# apresenta_o1.net
KiCad netlist of a schematic drawn in EAGLE
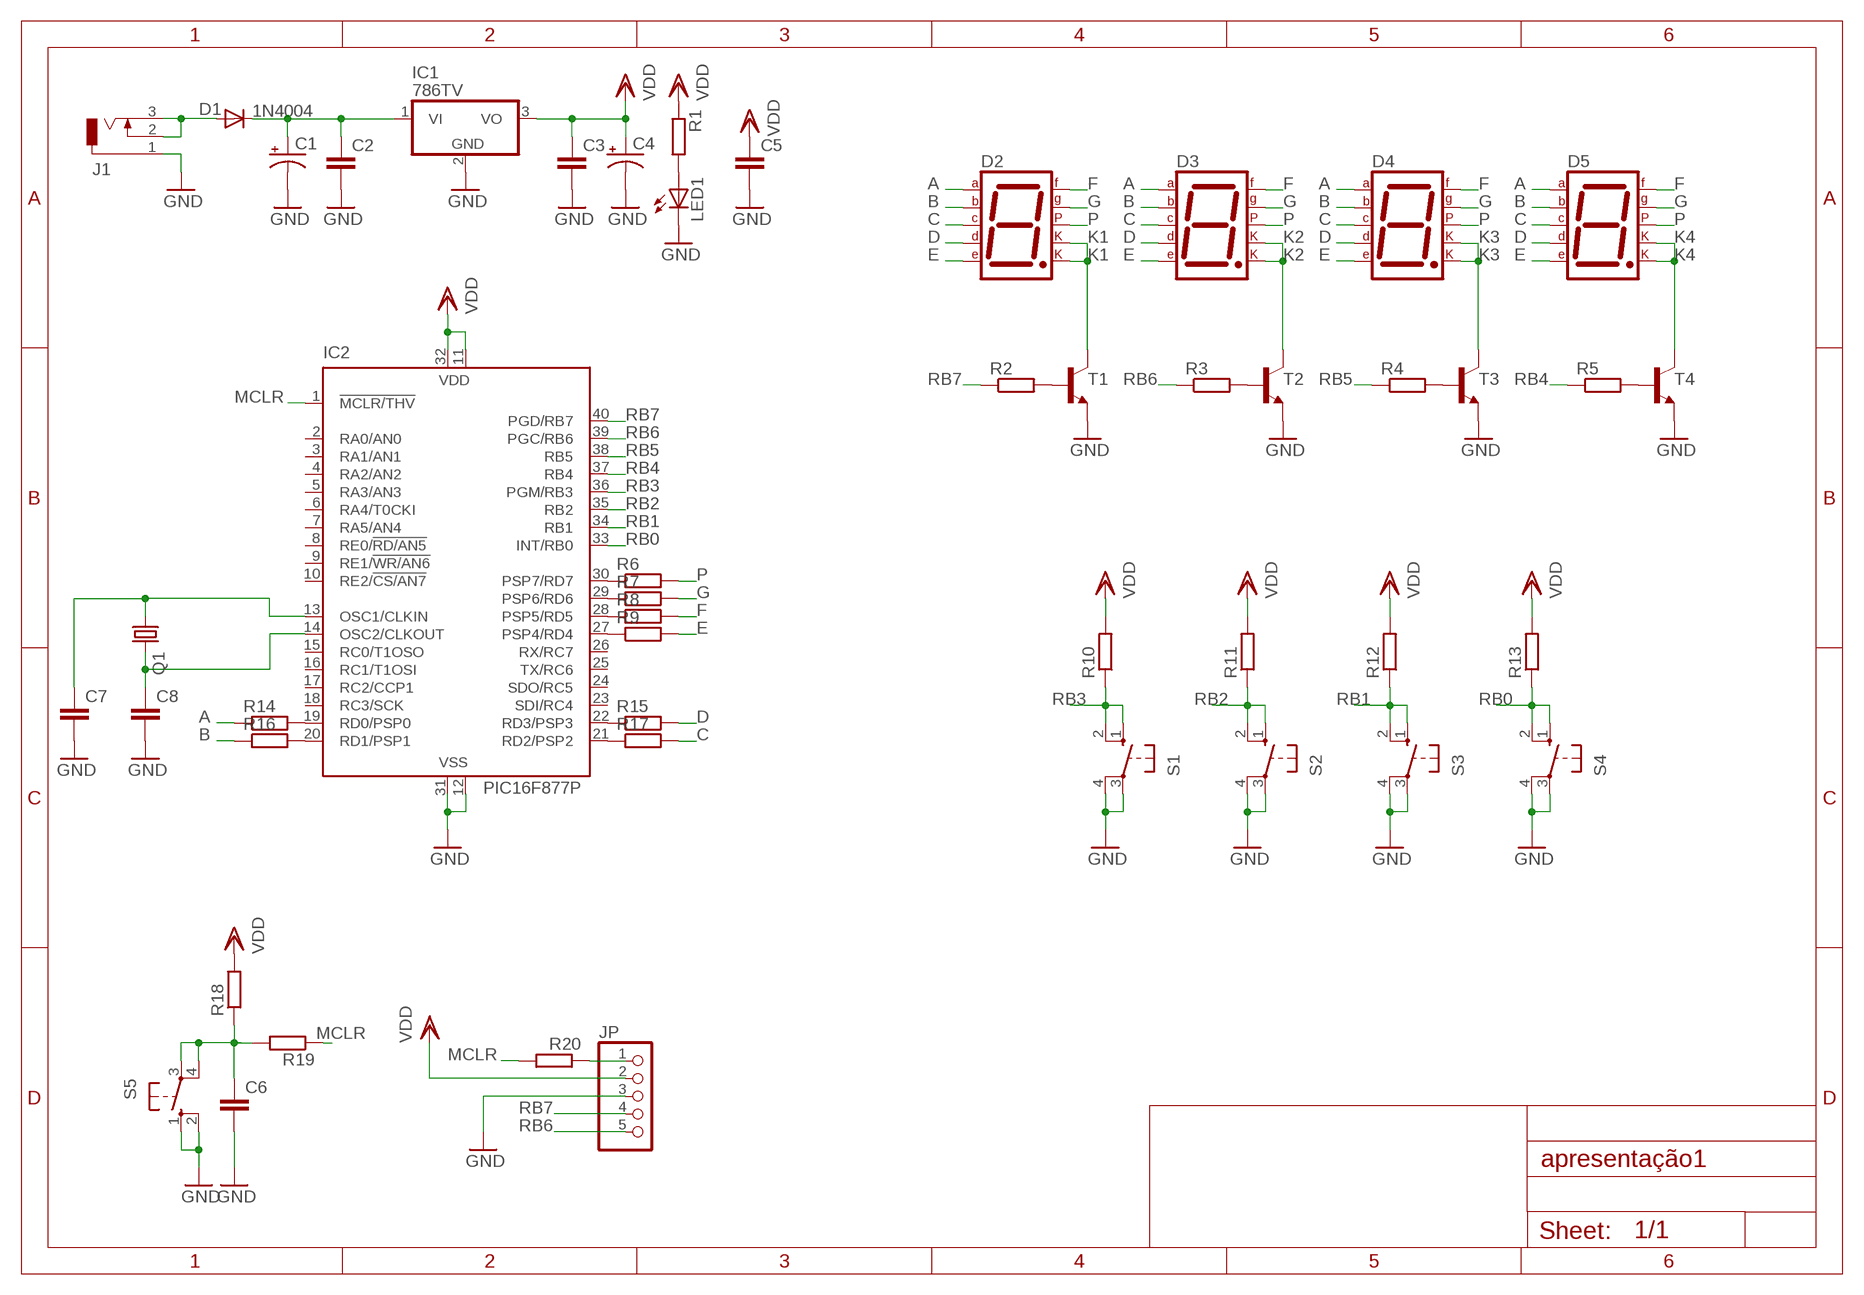
[diagram p0: schematic, sheet 1]

(export (version "E")
  (design (tool "Eeschema 10.0.6"))
  (components
    (comp (ref "C1")
      (value "CPOL-USE2.5-5")
      (footprint "eagle-import:E2,5-5")
      (libsource (lib "eagle-import") (part "CPOL-USE2.5-5"))
    )
    (comp (ref "C2")
      (value "C-EU025-025X050")
      (footprint "eagle-import:C025-025X050")
      (libsource (lib "eagle-import") (part "C-EU025-025X050"))
    )
    (comp (ref "C3")
      (value "C-EU025-025X050")
      (footprint "eagle-import:C025-025X050")
      (libsource (lib "eagle-import") (part "C-EU025-025X050"))
    )
    (comp (ref "C4")
      (value "CPOL-USE2.5-5")
      (footprint "eagle-import:E2,5-5")
      (libsource (lib "eagle-import") (part "CPOL-USE2.5-5"))
    )
    (comp (ref "C5")
      (value "C-EU025-025X050")
      (footprint "eagle-import:C025-025X050")
      (libsource (lib "eagle-import") (part "C-EU025-025X050"))
    )
    (comp (ref "C6")
      (value "C-EU025-025X050")
      (footprint "eagle-import:C025-025X050")
      (libsource (lib "eagle-import") (part "C-EU025-025X050"))
    )
    (comp (ref "C7")
      (value "C-EU025-025X050")
      (footprint "eagle-import:C025-025X050")
      (libsource (lib "eagle-import") (part "C-EU025-025X050"))
    )
    (comp (ref "C8")
      (value "C-EU025-025X050")
      (footprint "eagle-import:C025-025X050")
      (libsource (lib "eagle-import") (part "C-EU025-025X050"))
    )
    (comp (ref "D1")
      (value "1N4004")
      (footprint "eagle-import:DO41-10")
      (libsource (lib "eagle-import") (part "1N4004"))
    )
    (comp (ref "D2")
      (value "7SEG-CK")
      (footprint "eagle-import:7SEG-13")
      (libsource (lib "eagle-import") (part "7SEG-CK"))
    )
    (comp (ref "D3")
      (value "7SEG-CK")
      (footprint "eagle-import:7SEG-13")
      (libsource (lib "eagle-import") (part "7SEG-CK"))
    )
    (comp (ref "D4")
      (value "7SEG-CK")
      (footprint "eagle-import:7SEG-13")
      (libsource (lib "eagle-import") (part "7SEG-CK"))
    )
    (comp (ref "D5")
      (value "7SEG-CK")
      (footprint "eagle-import:7SEG-13")
      (libsource (lib "eagle-import") (part "7SEG-CK"))
    )
    (comp (ref "IC1")
      (value "786TV")
      (footprint "eagle-import:TO220V")
      (libsource (lib "eagle-import") (part "78TV6"))
    )
    (comp (ref "IC2")
      (value "PIC16F877P")
      (footprint "eagle-import:DIL40")
      (fields (field (name "MF") "MICROCHIP") (field (name "MPN") "PIC16F877-04/P"))
      (libsource (lib "eagle-import") (part "PIC16F87P7"))
    )
    (comp (ref "J1")
      (value "DCJ0303")
      (footprint "eagle-import:DCJ0303")
      (libsource (lib "eagle-import") (part "DCJ0303"))
    )
    (comp (ref "JP")
      (value "PINHD-1X5")
      (footprint "eagle-import:1X05")
      (libsource (lib "eagle-import") (part "PINHD-1X5"))
    )
    (comp (ref "LED1")
      (value "LED5MM")
      (footprint "eagle-import:LED5MM")
      (libsource (lib "eagle-import") (part "LED5MM"))
    )
    (comp (ref "Q1")
      (value "CRYSTALHC49S")
      (footprint "eagle-import:HC49_S")
      (libsource (lib "eagle-import") (part "CRYSTALHC49S"))
    )
    (comp (ref "R1")
      (value "R-EU_0204/7")
      (footprint "eagle-import:0204_7")
      (libsource (lib "eagle-import") (part "R-EU_0204/7"))
    )
    (comp (ref "R2")
      (value "R-EU_0204/7")
      (footprint "eagle-import:0204_7")
      (libsource (lib "eagle-import") (part "R-EU_0204/7"))
    )
    (comp (ref "R3")
      (value "R-EU_0204/7")
      (footprint "eagle-import:0204_7")
      (libsource (lib "eagle-import") (part "R-EU_0204/7"))
    )
    (comp (ref "R4")
      (value "R-EU_0204/7")
      (footprint "eagle-import:0204_7")
      (libsource (lib "eagle-import") (part "R-EU_0204/7"))
    )
    (comp (ref "R5")
      (value "R-EU_0204/7")
      (footprint "eagle-import:0204_7")
      (libsource (lib "eagle-import") (part "R-EU_0204/7"))
    )
    (comp (ref "R6")
      (value "R-EU_0204/7")
      (footprint "eagle-import:0204_7")
      (libsource (lib "eagle-import") (part "R-EU_0204/7"))
    )
    (comp (ref "R7")
      (value "R-EU_0204/7")
      (footprint "eagle-import:0204_7")
      (libsource (lib "eagle-import") (part "R-EU_0204/7"))
    )
    (comp (ref "R8")
      (value "R-EU_0204/7")
      (footprint "eagle-import:0204_7")
      (libsource (lib "eagle-import") (part "R-EU_0204/7"))
    )
    (comp (ref "R9")
      (value "R-EU_0204/7")
      (footprint "eagle-import:0204_7")
      (libsource (lib "eagle-import") (part "R-EU_0204/7"))
    )
    (comp (ref "R10")
      (value "R-EU_0204/7")
      (footprint "eagle-import:0204_7")
      (libsource (lib "eagle-import") (part "R-EU_0204/7"))
    )
    (comp (ref "R11")
      (value "R-EU_0204/7")
      (footprint "eagle-import:0204_7")
      (libsource (lib "eagle-import") (part "R-EU_0204/7"))
    )
    (comp (ref "R12")
      (value "R-EU_0204/7")
      (footprint "eagle-import:0204_7")
      (libsource (lib "eagle-import") (part "R-EU_0204/7"))
    )
    (comp (ref "R13")
      (value "R-EU_0204/7")
      (footprint "eagle-import:0204_7")
      (libsource (lib "eagle-import") (part "R-EU_0204/7"))
    )
    (comp (ref "R14")
      (value "R-EU_0204/7")
      (footprint "eagle-import:0204_7")
      (libsource (lib "eagle-import") (part "R-EU_0204/7"))
    )
    (comp (ref "R15")
      (value "R-EU_0204/7")
      (footprint "eagle-import:0204_7")
      (libsource (lib "eagle-import") (part "R-EU_0204/7"))
    )
    (comp (ref "R16")
      (value "R-EU_0204/7")
      (footprint "eagle-import:0204_7")
      (libsource (lib "eagle-import") (part "R-EU_0204/7"))
    )
    (comp (ref "R17")
      (value "R-EU_0204/7")
      (footprint "eagle-import:0204_7")
      (libsource (lib "eagle-import") (part "R-EU_0204/7"))
    )
    (comp (ref "R18")
      (value "R-EU_0204/7")
      (footprint "eagle-import:0204_7")
      (libsource (lib "eagle-import") (part "R-EU_0204/7"))
    )
    (comp (ref "R19")
      (value "R-EU_0204/7")
      (footprint "eagle-import:0204_7")
      (libsource (lib "eagle-import") (part "R-EU_0204/7"))
    )
    (comp (ref "R20")
      (value "R-EU_0204/7")
      (footprint "eagle-import:0204_7")
      (libsource (lib "eagle-import") (part "R-EU_0204/7"))
    )
    (comp (ref "S1")
      (value "10-XX")
      (footprint "eagle-import:B3F-10XX")
      (fields (field (name "MPN") "B3F-1000"))
      (libsource (lib "eagle-import") (part "10-XX"))
    )
    (comp (ref "S2")
      (value "10-XX")
      (footprint "eagle-import:B3F-10XX")
      (fields (field (name "MPN") "B3F-1000"))
      (libsource (lib "eagle-import") (part "10-XX"))
    )
    (comp (ref "S3")
      (value "10-XX")
      (footprint "eagle-import:B3F-10XX")
      (fields (field (name "MPN") "B3F-1000"))
      (libsource (lib "eagle-import") (part "10-XX"))
    )
    (comp (ref "S4")
      (value "10-XX")
      (footprint "eagle-import:B3F-10XX")
      (fields (field (name "MPN") "B3F-1000"))
      (libsource (lib "eagle-import") (part "10-XX"))
    )
    (comp (ref "S5")
      (value "10-XX")
      (footprint "eagle-import:B3F-10XX")
      (fields
        (field (name "MPN") "B3F-1000")
        (field (name "MPN_1") "B3F-1000")
        (field (name "OC_FARNELL") "176432")
        (field (name "OC_NEWARK") "36M3542")
      )
      (libsource (lib "eagle-import") (part "10-XX"))
    )
    (comp (ref "T1")
      (value "BC337-16-NPN-TO92-CBE")
      (footprint "eagle-import:TO92-CBE")
      (libsource (lib "eagle-import") (part "-NPN-TO92-CBEBC337-16"))
    )
    (comp (ref "T2")
      (value "BC337-16-NPN-TO92-CBE")
      (footprint "eagle-import:TO92-CBE")
      (libsource (lib "eagle-import") (part "-NPN-TO92-CBEBC337-16"))
    )
    (comp (ref "T3")
      (value "BC337-16-NPN-TO92-CBE")
      (footprint "eagle-import:TO92-CBE")
      (libsource (lib "eagle-import") (part "-NPN-TO92-CBEBC337-16"))
    )
    (comp (ref "T4")
      (value "BC337-16-NPN-TO92-CBE")
      (footprint "eagle-import:TO92-CBE")
      (libsource (lib "eagle-import") (part "-NPN-TO92-CBEBC337-16"))
    )
  )
  (nets
    (net (code "1") (name "/A") (class "Default")
      (node (ref "D2") (pin "7") (pinfunction "A_7") (pintype "passive"))
      (node (ref "D3") (pin "7") (pinfunction "A_7") (pintype "passive"))
      (node (ref "D4") (pin "7") (pinfunction "A_7") (pintype "passive"))
      (node (ref "D5") (pin "7") (pinfunction "A_7") (pintype "passive"))
      (node (ref "R14") (pin "1") (pinfunction "1_1") (pintype "passive"))
    )
    (net (code "2") (name "/B") (class "Default")
      (node (ref "D2") (pin "6") (pinfunction "B_6") (pintype "passive"))
      (node (ref "D3") (pin "6") (pinfunction "B_6") (pintype "passive"))
      (node (ref "D4") (pin "6") (pinfunction "B_6") (pintype "passive"))
      (node (ref "D5") (pin "6") (pinfunction "B_6") (pintype "passive"))
      (node (ref "R16") (pin "1") (pinfunction "1_1") (pintype "passive"))
    )
    (net (code "3") (name "/C") (class "Default")
      (node (ref "D2") (pin "4") (pinfunction "C_4") (pintype "passive"))
      (node (ref "D3") (pin "4") (pinfunction "C_4") (pintype "passive"))
      (node (ref "D4") (pin "4") (pinfunction "C_4") (pintype "passive"))
      (node (ref "D5") (pin "4") (pinfunction "C_4") (pintype "passive"))
      (node (ref "R17") (pin "2") (pinfunction "2_2") (pintype "passive"))
    )
    (net (code "4") (name "/D") (class "Default")
      (node (ref "D2") (pin "2") (pinfunction "D_2") (pintype "passive"))
      (node (ref "D3") (pin "2") (pinfunction "D_2") (pintype "passive"))
      (node (ref "D4") (pin "2") (pinfunction "D_2") (pintype "passive"))
      (node (ref "D5") (pin "2") (pinfunction "D_2") (pintype "passive"))
      (node (ref "R15") (pin "2") (pinfunction "2_2") (pintype "passive"))
    )
    (net (code "5") (name "/E") (class "Default")
      (node (ref "D2") (pin "1") (pinfunction "E_1") (pintype "passive"))
      (node (ref "D3") (pin "1") (pinfunction "E_1") (pintype "passive"))
      (node (ref "D4") (pin "1") (pinfunction "E_1") (pintype "passive"))
      (node (ref "D5") (pin "1") (pinfunction "E_1") (pintype "passive"))
      (node (ref "R9") (pin "2") (pinfunction "2_2") (pintype "passive"))
    )
    (net (code "6") (name "/F") (class "Default")
      (node (ref "D2") (pin "9") (pinfunction "F_9") (pintype "passive"))
      (node (ref "D3") (pin "9") (pinfunction "F_9") (pintype "passive"))
      (node (ref "D4") (pin "9") (pinfunction "F_9") (pintype "passive"))
      (node (ref "D5") (pin "9") (pinfunction "F_9") (pintype "passive"))
      (node (ref "R8") (pin "2") (pinfunction "2_2") (pintype "passive"))
    )
    (net (code "7") (name "/G") (class "Default")
      (node (ref "D2") (pin "10") (pinfunction "G_10") (pintype "passive"))
      (node (ref "D3") (pin "10") (pinfunction "G_10") (pintype "passive"))
      (node (ref "D4") (pin "10") (pinfunction "G_10") (pintype "passive"))
      (node (ref "D5") (pin "10") (pinfunction "G_10") (pintype "passive"))
      (node (ref "R7") (pin "2") (pinfunction "2_2") (pintype "passive"))
    )
    (net (code "8") (name "/K1") (class "Default")
      (node (ref "D2") (pin "3") (pinfunction "CK1_3") (pintype "passive"))
      (node (ref "D2") (pin "8") (pinfunction "CK2_8") (pintype "passive"))
      (node (ref "T1") (pin "C") (pinfunction "C_C") (pintype "passive"))
    )
    (net (code "9") (name "/K2") (class "Default")
      (node (ref "D3") (pin "3") (pinfunction "CK1_3") (pintype "passive"))
      (node (ref "D3") (pin "8") (pinfunction "CK2_8") (pintype "passive"))
      (node (ref "T2") (pin "C") (pinfunction "C_C") (pintype "passive"))
    )
    (net (code "10") (name "/K3") (class "Default")
      (node (ref "D4") (pin "3") (pinfunction "CK1_3") (pintype "passive"))
      (node (ref "D4") (pin "8") (pinfunction "CK2_8") (pintype "passive"))
      (node (ref "T3") (pin "C") (pinfunction "C_C") (pintype "passive"))
    )
    (net (code "11") (name "/K4") (class "Default")
      (node (ref "D5") (pin "3") (pinfunction "CK1_3") (pintype "passive"))
      (node (ref "D5") (pin "8") (pinfunction "CK2_8") (pintype "passive"))
      (node (ref "T4") (pin "C") (pinfunction "C_C") (pintype "passive"))
    )
    (net (code "12") (name "/MCLR") (class "Default")
      (node (ref "IC2") (pin "1") (pinfunction "~{MCLR/THV}_1") (pintype "input"))
      (node (ref "R19") (pin "1") (pinfunction "1_1") (pintype "passive"))
      (node (ref "R20") (pin "2") (pinfunction "2_2") (pintype "passive"))
    )
    (net (code "13") (name "/P") (class "Default")
      (node (ref "D2") (pin "5") (pinfunction "DP_5") (pintype "passive"))
      (node (ref "D3") (pin "5") (pinfunction "DP_5") (pintype "passive"))
      (node (ref "D4") (pin "5") (pinfunction "DP_5") (pintype "passive"))
      (node (ref "D5") (pin "5") (pinfunction "DP_5") (pintype "passive"))
      (node (ref "R6") (pin "2") (pinfunction "2_2") (pintype "passive"))
    )
    (net (code "14") (name "/RB0") (class "Default")
      (node (ref "IC2") (pin "33") (pinfunction "INT/RB0_33") (pintype "bidirectional"))
      (node (ref "R13") (pin "1") (pinfunction "1_1") (pintype "passive"))
      (node (ref "S4") (pin "1") (pinfunction "S_1") (pintype "passive"))
      (node (ref "S4") (pin "2") (pinfunction "S1_2") (pintype "passive"))
    )
    (net (code "15") (name "/RB1") (class "Default")
      (node (ref "IC2") (pin "34") (pinfunction "RB1_34") (pintype "bidirectional"))
      (node (ref "R12") (pin "1") (pinfunction "1_1") (pintype "passive"))
      (node (ref "S3") (pin "1") (pinfunction "S_1") (pintype "passive"))
      (node (ref "S3") (pin "2") (pinfunction "S1_2") (pintype "passive"))
    )
    (net (code "16") (name "/RB2") (class "Default")
      (node (ref "IC2") (pin "35") (pinfunction "RB2_35") (pintype "bidirectional"))
      (node (ref "R11") (pin "1") (pinfunction "1_1") (pintype "passive"))
      (node (ref "S2") (pin "1") (pinfunction "S_1") (pintype "passive"))
      (node (ref "S2") (pin "2") (pinfunction "S1_2") (pintype "passive"))
    )
    (net (code "17") (name "/RB3") (class "Default")
      (node (ref "IC2") (pin "36") (pinfunction "PGM/RB3_36") (pintype "bidirectional"))
      (node (ref "R10") (pin "1") (pinfunction "1_1") (pintype "passive"))
      (node (ref "S1") (pin "1") (pinfunction "S_1") (pintype "passive"))
      (node (ref "S1") (pin "2") (pinfunction "S1_2") (pintype "passive"))
    )
    (net (code "18") (name "/RB4") (class "Default")
      (node (ref "IC2") (pin "37") (pinfunction "RB4_37") (pintype "bidirectional"))
      (node (ref "R5") (pin "1") (pinfunction "1_1") (pintype "passive"))
    )
    (net (code "19") (name "/RB5") (class "Default")
      (node (ref "IC2") (pin "38") (pinfunction "RB5_38") (pintype "bidirectional"))
      (node (ref "R4") (pin "1") (pinfunction "1_1") (pintype "passive"))
    )
    (net (code "20") (name "/RB6") (class "Default")
      (node (ref "IC2") (pin "39") (pinfunction "PGC/RB6_39") (pintype "bidirectional"))
      (node (ref "JP") (pin "5") (pinfunction "5_5") (pintype "passive"))
      (node (ref "R3") (pin "1") (pinfunction "1_1") (pintype "passive"))
    )
    (net (code "21") (name "/RB7") (class "Default")
      (node (ref "IC2") (pin "40") (pinfunction "PGD/RB7_40") (pintype "bidirectional"))
      (node (ref "JP") (pin "4") (pinfunction "4_4") (pintype "passive"))
      (node (ref "R2") (pin "1") (pinfunction "1_1") (pintype "passive"))
    )
    (net (code "22") (name "GND") (class "Default")
      (node (ref "C1") (pin "-") (pinfunction "-_-") (pintype "passive"))
      (node (ref "C2") (pin "2") (pinfunction "2_2") (pintype "passive"))
      (node (ref "C3") (pin "2") (pinfunction "2_2") (pintype "passive"))
      (node (ref "C4") (pin "-") (pinfunction "-_-") (pintype "passive"))
      (node (ref "C5") (pin "2") (pinfunction "2_2") (pintype "passive"))
      (node (ref "C6") (pin "2") (pinfunction "2_2") (pintype "passive"))
      (node (ref "C7") (pin "2") (pinfunction "2_2") (pintype "passive"))
      (node (ref "C8") (pin "2") (pinfunction "2_2") (pintype "passive"))
      (node (ref "IC1") (pin "2") (pinfunction "GND_2") (pintype "passive"))
      (node (ref "IC2") (pin "12") (pinfunction "VSS_12") (pintype "power_in"))
      (node (ref "IC2") (pin "31") (pinfunction "VSS_31") (pintype "power_in"))
      (node (ref "J1") (pin "1") (pinfunction "1_1") (pintype "passive"))
      (node (ref "JP") (pin "3") (pinfunction "3_3") (pintype "passive"))
      (node (ref "LED1") (pin "K") (pinfunction "C_K") (pintype "passive"))
      (node (ref "S1") (pin "3") (pinfunction "P_3") (pintype "passive"))
      (node (ref "S1") (pin "4") (pinfunction "P1_4") (pintype "passive"))
      (node (ref "S2") (pin "3") (pinfunction "P_3") (pintype "passive"))
      (node (ref "S2") (pin "4") (pinfunction "P1_4") (pintype "passive"))
      (node (ref "S3") (pin "3") (pinfunction "P_3") (pintype "passive"))
      (node (ref "S3") (pin "4") (pinfunction "P1_4") (pintype "passive"))
      (node (ref "S4") (pin "3") (pinfunction "P_3") (pintype "passive"))
      (node (ref "S4") (pin "4") (pinfunction "P1_4") (pintype "passive"))
      (node (ref "S5") (pin "1") (pinfunction "S_1") (pintype "passive"))
      (node (ref "S5") (pin "2") (pinfunction "S1_2") (pintype "passive"))
      (node (ref "T1") (pin "E") (pinfunction "E_E") (pintype "passive"))
      (node (ref "T2") (pin "E") (pinfunction "E_E") (pintype "passive"))
      (node (ref "T3") (pin "E") (pinfunction "E_E") (pintype "passive"))
      (node (ref "T4") (pin "E") (pinfunction "E_E") (pintype "passive"))
    )
    (net (code "23") (name "Net-(D1-PadA)") (class "Default")
      (node (ref "D1") (pin "A") (pinfunction "A_A") (pintype "passive"))
      (node (ref "J1") (pin "2") (pinfunction "2_2") (pintype "passive"))
      (node (ref "J1") (pin "3") (pinfunction "3_3") (pintype "passive"))
    )
    (net (code "24") (name "Net-(IC1-VI)") (class "Default")
      (node (ref "C1") (pin "+") (pinfunction "+_+") (pintype "passive"))
      (node (ref "C2") (pin "1") (pinfunction "1_1") (pintype "passive"))
      (node (ref "D1") (pin "C") (pinfunction "C_C") (pintype "passive"))
      (node (ref "IC1") (pin "1") (pinfunction "VI_1") (pintype "input"))
    )
    (net (code "25") (name "Net-(IC2-OSC1{slash}CLKIN)") (class "Default")
      (node (ref "C7") (pin "1") (pinfunction "1_1") (pintype "passive"))
      (node (ref "IC2") (pin "13") (pinfunction "OSC1/CLKIN_13") (pintype "input"))
      (node (ref "Q1") (pin "1") (pinfunction "1_1") (pintype "passive"))
    )
    (net (code "26") (name "Net-(IC2-OSC2{slash}CLKOUT)") (class "Default")
      (node (ref "C8") (pin "1") (pinfunction "1_1") (pintype "passive"))
      (node (ref "IC2") (pin "14") (pinfunction "OSC2/CLKOUT_14") (pintype "output"))
      (node (ref "Q1") (pin "2") (pinfunction "2_2") (pintype "passive"))
    )
    (net (code "27") (name "Net-(IC2-PSP4{slash}RD4)") (class "Default")
      (node (ref "IC2") (pin "27") (pinfunction "PSP4/RD4_27") (pintype "bidirectional"))
      (node (ref "R9") (pin "1") (pinfunction "1_1") (pintype "passive"))
    )
    (net (code "28") (name "Net-(IC2-PSP5{slash}RD5)") (class "Default")
      (node (ref "IC2") (pin "28") (pinfunction "PSP5/RD5_28") (pintype "bidirectional"))
      (node (ref "R8") (pin "1") (pinfunction "1_1") (pintype "passive"))
    )
    (net (code "29") (name "Net-(IC2-PSP6{slash}RD6)") (class "Default")
      (node (ref "IC2") (pin "29") (pinfunction "PSP6/RD6_29") (pintype "bidirectional"))
      (node (ref "R7") (pin "1") (pinfunction "1_1") (pintype "passive"))
    )
    (net (code "30") (name "Net-(IC2-PSP7{slash}RD7)") (class "Default")
      (node (ref "IC2") (pin "30") (pinfunction "PSP7/RD7_30") (pintype "bidirectional"))
      (node (ref "R6") (pin "1") (pinfunction "1_1") (pintype "passive"))
    )
    (net (code "31") (name "Net-(IC2-RD0{slash}PSP0)") (class "Default")
      (node (ref "IC2") (pin "19") (pinfunction "RD0/PSP0_19") (pintype "bidirectional"))
      (node (ref "R14") (pin "2") (pinfunction "2_2") (pintype "passive"))
    )
    (net (code "32") (name "Net-(IC2-RD1{slash}PSP1)") (class "Default")
      (node (ref "IC2") (pin "20") (pinfunction "RD1/PSP1_20") (pintype "bidirectional"))
      (node (ref "R16") (pin "2") (pinfunction "2_2") (pintype "passive"))
    )
    (net (code "33") (name "Net-(IC2-RD2{slash}PSP2)") (class "Default")
      (node (ref "IC2") (pin "21") (pinfunction "RD2/PSP2_21") (pintype "bidirectional"))
      (node (ref "R17") (pin "1") (pinfunction "1_1") (pintype "passive"))
    )
    (net (code "34") (name "Net-(IC2-RD3{slash}PSP3)") (class "Default")
      (node (ref "IC2") (pin "22") (pinfunction "RD3/PSP3_22") (pintype "bidirectional"))
      (node (ref "R15") (pin "1") (pinfunction "1_1") (pintype "passive"))
    )
    (net (code "35") (name "Net-(JP-Pad1)") (class "Default")
      (node (ref "JP") (pin "1") (pinfunction "1_1") (pintype "passive"))
      (node (ref "R20") (pin "1") (pinfunction "1_1") (pintype "passive"))
    )
    (net (code "36") (name "Net-(LED1-PadA)") (class "Default")
      (node (ref "LED1") (pin "A") (pinfunction "A_A") (pintype "passive"))
      (node (ref "R1") (pin "2") (pinfunction "2_2") (pintype "passive"))
    )
    (net (code "37") (name "Net-(R2-Pad2)") (class "Default")
      (node (ref "R2") (pin "2") (pinfunction "2_2") (pintype "passive"))
      (node (ref "T1") (pin "B") (pinfunction "B_B") (pintype "passive"))
    )
    (net (code "38") (name "Net-(R3-Pad2)") (class "Default")
      (node (ref "R3") (pin "2") (pinfunction "2_2") (pintype "passive"))
      (node (ref "T2") (pin "B") (pinfunction "B_B") (pintype "passive"))
    )
    (net (code "39") (name "Net-(R4-Pad2)") (class "Default")
      (node (ref "R4") (pin "2") (pinfunction "2_2") (pintype "passive"))
      (node (ref "T3") (pin "B") (pinfunction "B_B") (pintype "passive"))
    )
    (net (code "40") (name "Net-(R5-Pad2)") (class "Default")
      (node (ref "R5") (pin "2") (pinfunction "2_2") (pintype "passive"))
      (node (ref "T4") (pin "B") (pinfunction "B_B") (pintype "passive"))
    )
    (net (code "41") (name "Net-(S5-P)") (class "Default")
      (node (ref "C6") (pin "1") (pinfunction "1_1") (pintype "passive"))
      (node (ref "R18") (pin "1") (pinfunction "1_1") (pintype "passive"))
      (node (ref "R19") (pin "2") (pinfunction "2_2") (pintype "passive"))
      (node (ref "S5") (pin "3") (pinfunction "P_3") (pintype "passive"))
      (node (ref "S5") (pin "4") (pinfunction "P1_4") (pintype "passive"))
    )
    (net (code "42") (name "VDD") (class "Default")
      (node (ref "C3") (pin "1") (pinfunction "1_1") (pintype "passive"))
      (node (ref "C4") (pin "+") (pinfunction "+_+") (pintype "passive"))
      (node (ref "C5") (pin "1") (pinfunction "1_1") (pintype "passive"))
      (node (ref "IC1") (pin "3") (pinfunction "VO_3") (pintype "passive"))
      (node (ref "IC2") (pin "11") (pinfunction "VDD_11") (pintype "power_in"))
      (node (ref "IC2") (pin "32") (pinfunction "VDD_32") (pintype "power_in"))
      (node (ref "JP") (pin "2") (pinfunction "2_2") (pintype "passive"))
      (node (ref "R1") (pin "1") (pinfunction "1_1") (pintype "passive"))
      (node (ref "R10") (pin "2") (pinfunction "2_2") (pintype "passive"))
      (node (ref "R11") (pin "2") (pinfunction "2_2") (pintype "passive"))
      (node (ref "R12") (pin "2") (pinfunction "2_2") (pintype "passive"))
      (node (ref "R13") (pin "2") (pinfunction "2_2") (pintype "passive"))
      (node (ref "R18") (pin "2") (pinfunction "2_2") (pintype "passive"))
    )
    (net (code "43") (name "unconnected-(IC2-RA0{slash}AN0-Pad2)") (class "Default")
      (node (ref "IC2") (pin "2") (pinfunction "RA0/AN0_2") (pintype "bidirectional"))
    )
    (net (code "44") (name "unconnected-(IC2-RA1{slash}AN1-Pad3)") (class "Default")
      (node (ref "IC2") (pin "3") (pinfunction "RA1/AN1_3") (pintype "bidirectional"))
    )
    (net (code "45") (name "unconnected-(IC2-RA2{slash}AN2-Pad4)") (class "Default")
      (node (ref "IC2") (pin "4") (pinfunction "RA2/AN2_4") (pintype "bidirectional"))
    )
    (net (code "46") (name "unconnected-(IC2-RA3{slash}AN3-Pad5)") (class "Default")
      (node (ref "IC2") (pin "5") (pinfunction "RA3/AN3_5") (pintype "bidirectional"))
    )
    (net (code "47") (name "unconnected-(IC2-RA4{slash}T0CKI-Pad6)") (class "Default")
      (node (ref "IC2") (pin "6") (pinfunction "RA4/T0CKI_6") (pintype "bidirectional"))
    )
    (net (code "48") (name "unconnected-(IC2-RA5{slash}AN4-Pad7)") (class "Default")
      (node (ref "IC2") (pin "7") (pinfunction "RA5/AN4_7") (pintype "bidirectional"))
    )
    (net (code "49") (name "unconnected-(IC2-RC0{slash}T1OSO-Pad15)") (class "Default")
      (node (ref "IC2") (pin "15") (pinfunction "RC0/T1OSO_15") (pintype "bidirectional"))
    )
    (net (code "50") (name "unconnected-(IC2-RC1{slash}T1OSI-Pad16)") (class "Default")
      (node (ref "IC2") (pin "16") (pinfunction "RC1/T1OSI_16") (pintype "bidirectional"))
    )
    (net (code "51") (name "unconnected-(IC2-RC2{slash}CCP1-Pad17)") (class "Default")
      (node (ref "IC2") (pin "17") (pinfunction "RC2/CCP1_17") (pintype "bidirectional"))
    )
    (net (code "52") (name "unconnected-(IC2-RC3{slash}SCK-Pad18)") (class "Default")
      (node (ref "IC2") (pin "18") (pinfunction "RC3/SCK_18") (pintype "bidirectional"))
    )
    (net (code "53") (name "unconnected-(IC2-RE0{slash}~{RD{slash}AN5}-Pad8)") (class "Default")
      (node (ref "IC2") (pin "8") (pinfunction "RE0/~{RD/AN5}_8") (pintype "bidirectional"))
    )
    (net (code "54") (name "unconnected-(IC2-RE1{slash}~{WR{slash}AN6}-Pad9)") (class "Default")
      (node (ref "IC2") (pin "9") (pinfunction "RE1/~{WR/AN6}_9") (pintype "bidirectional"))
    )
    (net (code "55") (name "unconnected-(IC2-RE2{slash}~{CS{slash}AN7}-Pad10)") (class "Default")
      (node (ref "IC2") (pin "10") (pinfunction "RE2/~{CS/AN7}_10") (pintype "bidirectional"))
    )
    (net (code "56") (name "unconnected-(IC2-RX{slash}RC7-Pad26)") (class "Default")
      (node (ref "IC2") (pin "26") (pinfunction "RX/RC7_26") (pintype "bidirectional"))
    )
    (net (code "57") (name "unconnected-(IC2-SDI{slash}RC4-Pad23)") (class "Default")
      (node (ref "IC2") (pin "23") (pinfunction "SDI/RC4_23") (pintype "bidirectional"))
    )
    (net (code "58") (name "unconnected-(IC2-SDO{slash}RC5-Pad24)") (class "Default")
      (node (ref "IC2") (pin "24") (pinfunction "SDO/RC5_24") (pintype "bidirectional"))
    )
    (net (code "59") (name "unconnected-(IC2-TX{slash}RC6-Pad25)") (class "Default")
      (node (ref "IC2") (pin "25") (pinfunction "TX/RC6_25") (pintype "bidirectional"))
    )
  )
)
